# esc.net
KiCad netlist of a schematic drawn in EAGLE
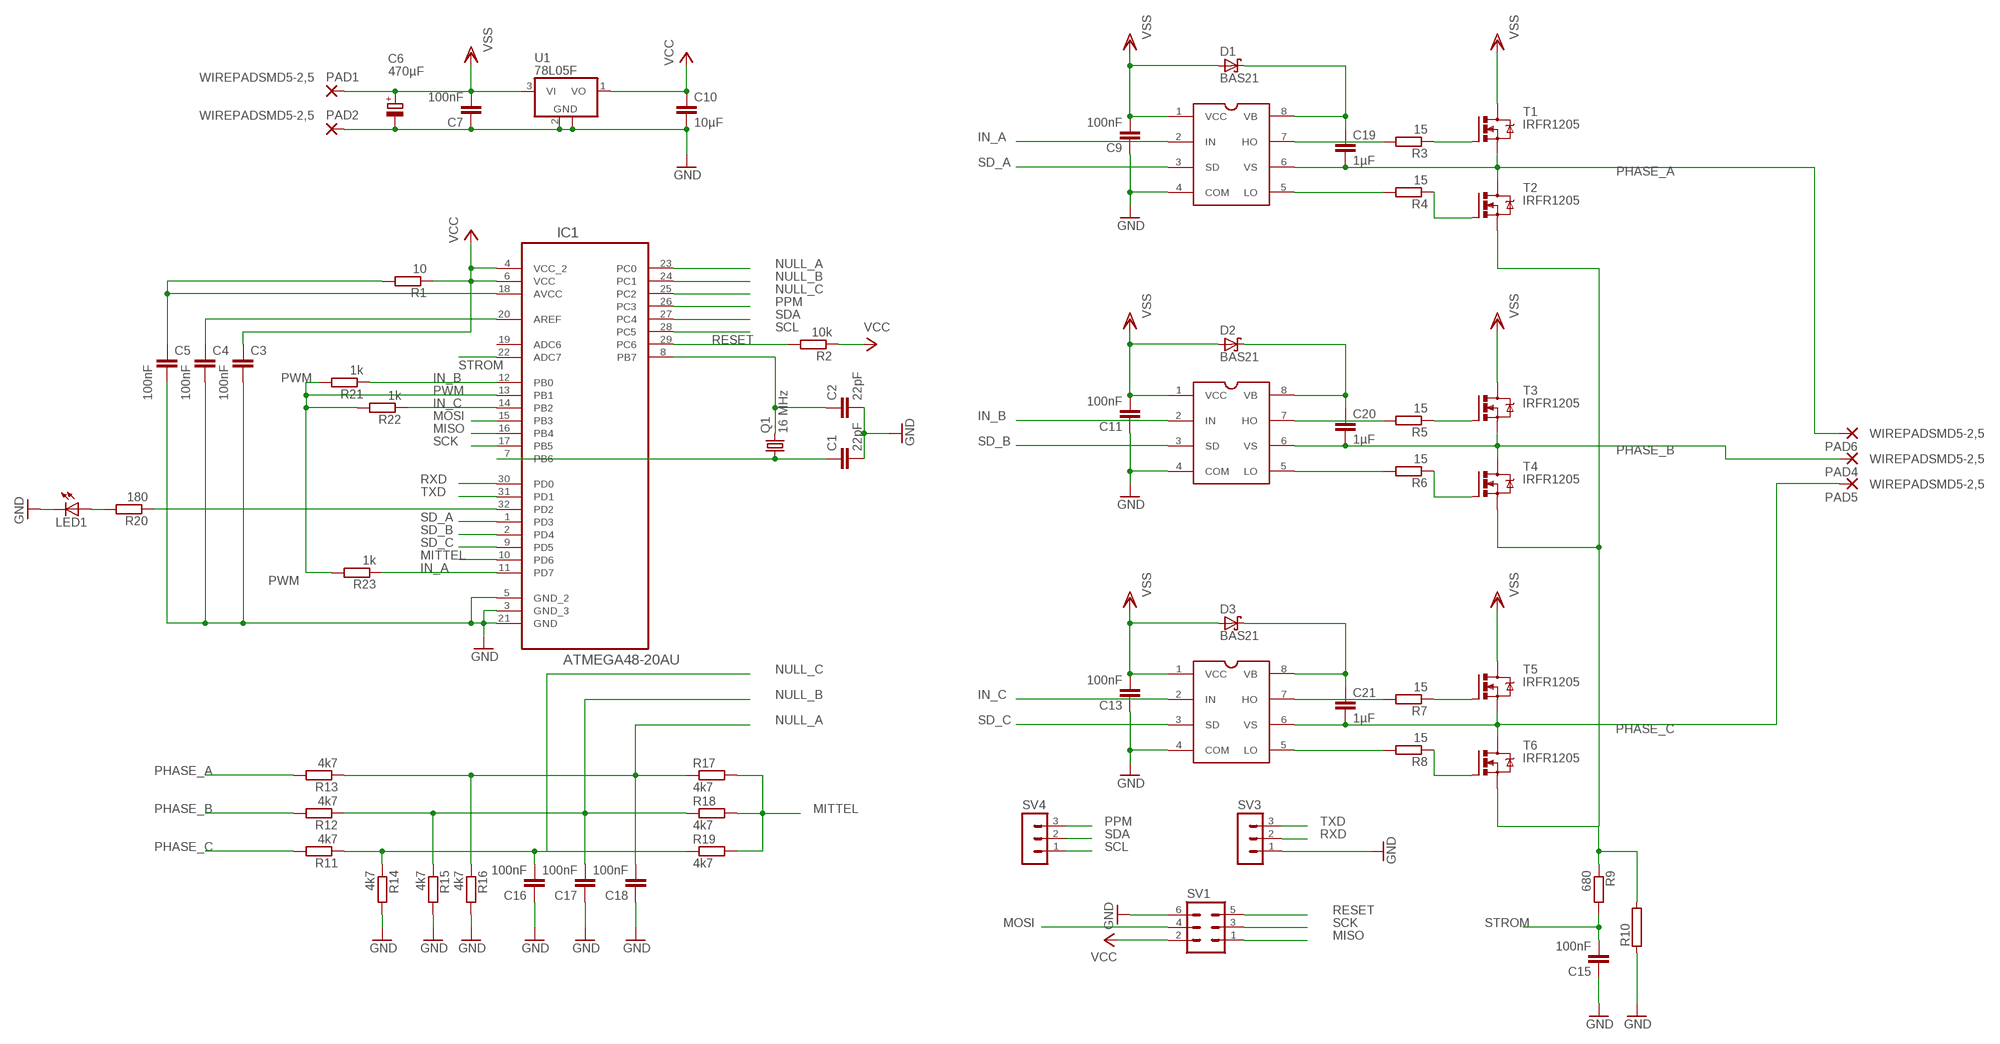
[diagram p0: schematic, sheet 1]

(export (version "E")
  (design (tool "Eeschema 10.0.6"))
  (components
    (comp (ref "C1")
      (value "22pF")
      (footprint "eagle-import:C1206")
      (libsource (lib "eagle-import") (part "C-EUC1206"))
    )
    (comp (ref "C2")
      (value "22pF")
      (footprint "eagle-import:C1206")
      (libsource (lib "eagle-import") (part "C-EUC1206"))
    )
    (comp (ref "C3")
      (value "100nF")
      (footprint "eagle-import:C1206")
      (libsource (lib "eagle-import") (part "C-EUC1206"))
    )
    (comp (ref "C4")
      (value "100nF")
      (footprint "eagle-import:C1206")
      (libsource (lib "eagle-import") (part "C-EUC1206"))
    )
    (comp (ref "C5")
      (value "100nF")
      (footprint "eagle-import:C1206")
      (libsource (lib "eagle-import") (part "C-EUC1206"))
    )
    (comp (ref "C6")
      (value "470µF")
      (footprint "eagle-import:E5-10,5")
      (libsource (lib "eagle-import") (part "CPOL-EUE5-10.5"))
    )
    (comp (ref "C7")
      (value "100nF")
      (footprint "eagle-import:C1206")
      (libsource (lib "eagle-import") (part "C-EUC1206"))
    )
    (comp (ref "C9")
      (value "100nF")
      (footprint "eagle-import:C1206")
      (libsource (lib "eagle-import") (part "C-EUC1206"))
    )
    (comp (ref "C10")
      (value "10µF")
      (footprint "eagle-import:C1206")
      (libsource (lib "eagle-import") (part "C-EUC1206"))
    )
    (comp (ref "C11")
      (value "100nF")
      (footprint "eagle-import:C1206")
      (libsource (lib "eagle-import") (part "C-EUC1206"))
    )
    (comp (ref "C13")
      (value "100nF")
      (footprint "eagle-import:C1206")
      (libsource (lib "eagle-import") (part "C-EUC1206"))
    )
    (comp (ref "C15")
      (value "100nF")
      (footprint "eagle-import:C1206")
      (libsource (lib "eagle-import") (part "C-EUC1206"))
    )
    (comp (ref "C16")
      (value "100nF")
      (footprint "eagle-import:C1206")
      (libsource (lib "eagle-import") (part "C-EUC1206"))
    )
    (comp (ref "C17")
      (value "100nF")
      (footprint "eagle-import:C1206")
      (libsource (lib "eagle-import") (part "C-EUC1206"))
    )
    (comp (ref "C18")
      (value "100nF")
      (footprint "eagle-import:C1206")
      (libsource (lib "eagle-import") (part "C-EUC1206"))
    )
    (comp (ref "C19")
      (value "1µF")
      (footprint "eagle-import:C1206")
      (libsource (lib "eagle-import") (part "C-EUC1206"))
    )
    (comp (ref "C20")
      (value "1µF")
      (footprint "eagle-import:C1206")
      (libsource (lib "eagle-import") (part "C-EUC1206"))
    )
    (comp (ref "C21")
      (value "1µF")
      (footprint "eagle-import:C1206")
      (libsource (lib "eagle-import") (part "C-EUC1206"))
    )
    (comp (ref "D1")
      (value "BAS21")
      (footprint "eagle-import:SOT23")
      (libsource (lib "eagle-import") (part "BAS40"))
    )
    (comp (ref "D2")
      (value "BAS21")
      (footprint "eagle-import:SOT23")
      (libsource (lib "eagle-import") (part "BAS40"))
    )
    (comp (ref "D3")
      (value "BAS21")
      (footprint "eagle-import:SOT23")
      (libsource (lib "eagle-import") (part "BAS40"))
    )
    (comp (ref "IC1")
      (value "ATMEGA48-20AU")
      (footprint "eagle-import:QFP80P900X900X120-32N")
      (libsource (lib "eagle-import") (part "ATMEGA48-20AU"))
    )
    (comp (ref "LED1")
      (value "LEDCHIPLED_1206")
      (footprint "eagle-import:CHIPLED_1206")
      (libsource (lib "eagle-import") (part "LEDCHIPLED_1206"))
    )
    (comp (ref "PAD1")
      (value "WIREPADSMD5-2,5")
      (footprint "eagle-import:5-2,5")
      (libsource (lib "eagle-import") (part "WIREPADSMD5-2,5"))
    )
    (comp (ref "PAD2")
      (value "WIREPADSMD5-2,5")
      (footprint "eagle-import:5-2,5")
      (libsource (lib "eagle-import") (part "WIREPADSMD5-2,5"))
    )
    (comp (ref "PAD4")
      (value "WIREPADSMD5-2,5")
      (footprint "eagle-import:5-2,5")
      (libsource (lib "eagle-import") (part "WIREPADSMD5-2,5"))
    )
    (comp (ref "PAD5")
      (value "WIREPADSMD5-2,5")
      (footprint "eagle-import:5-2,5")
      (libsource (lib "eagle-import") (part "WIREPADSMD5-2,5"))
    )
    (comp (ref "PAD6")
      (value "WIREPADSMD5-2,5")
      (footprint "eagle-import:5-2,5")
      (libsource (lib "eagle-import") (part "WIREPADSMD5-2,5"))
    )
    (comp (ref "Q1")
      (value "16 MHz")
      (footprint "eagle-import:HC49UP")
      (libsource (lib "eagle-import") (part "CRYSTALHC49UP"))
    )
    (comp (ref "R1")
      (value "10")
      (footprint "eagle-import:R1206")
      (libsource (lib "eagle-import") (part "R-EU_R1206"))
    )
    (comp (ref "R2")
      (value "10k")
      (footprint "eagle-import:R1206")
      (libsource (lib "eagle-import") (part "R-EU_R1206"))
    )
    (comp (ref "R3")
      (value "15")
      (footprint "eagle-import:R1206")
      (libsource (lib "eagle-import") (part "R-EU_R1206"))
    )
    (comp (ref "R4")
      (value "15")
      (footprint "eagle-import:R1206")
      (libsource (lib "eagle-import") (part "R-EU_R1206"))
    )
    (comp (ref "R5")
      (value "15")
      (footprint "eagle-import:R1206")
      (libsource (lib "eagle-import") (part "R-EU_R1206"))
    )
    (comp (ref "R6")
      (value "15")
      (footprint "eagle-import:R1206")
      (libsource (lib "eagle-import") (part "R-EU_R1206"))
    )
    (comp (ref "R7")
      (value "15")
      (footprint "eagle-import:R1206")
      (libsource (lib "eagle-import") (part "R-EU_R1206"))
    )
    (comp (ref "R8")
      (value "15")
      (footprint "eagle-import:R1206")
      (libsource (lib "eagle-import") (part "R-EU_R1206"))
    )
    (comp (ref "R9")
      (value "680")
      (footprint "eagle-import:R1206")
      (libsource (lib "eagle-import") (part "R-EU_R1206"))
    )
    (comp (ref "R10")
      (value "RCA5150")
      (footprint "eagle-import:CA5150")
      (libsource (lib "eagle-import") (part "RCA5150"))
    )
    (comp (ref "R11")
      (value "4k7")
      (footprint "eagle-import:R1206")
      (libsource (lib "eagle-import") (part "R-EU_R1206"))
    )
    (comp (ref "R12")
      (value "4k7")
      (footprint "eagle-import:R1206")
      (libsource (lib "eagle-import") (part "R-EU_R1206"))
    )
    (comp (ref "R13")
      (value "4k7")
      (footprint "eagle-import:R1206")
      (libsource (lib "eagle-import") (part "R-EU_R1206"))
    )
    (comp (ref "R14")
      (value "4k7")
      (footprint "eagle-import:R1206")
      (libsource (lib "eagle-import") (part "R-EU_R1206"))
    )
    (comp (ref "R15")
      (value "4k7")
      (footprint "eagle-import:R1206")
      (libsource (lib "eagle-import") (part "R-EU_R1206"))
    )
    (comp (ref "R16")
      (value "4k7")
      (footprint "eagle-import:R1206")
      (libsource (lib "eagle-import") (part "R-EU_R1206"))
    )
    (comp (ref "R17")
      (value "4k7")
      (footprint "eagle-import:R1206")
      (libsource (lib "eagle-import") (part "R-EU_R1206"))
    )
    (comp (ref "R18")
      (value "4k7")
      (footprint "eagle-import:R1206")
      (libsource (lib "eagle-import") (part "R-EU_R1206"))
    )
    (comp (ref "R19")
      (value "4k7")
      (footprint "eagle-import:R1206")
      (libsource (lib "eagle-import") (part "R-EU_R1206"))
    )
    (comp (ref "R20")
      (value "180")
      (footprint "eagle-import:R1206")
      (libsource (lib "eagle-import") (part "R-EU_R1206"))
    )
    (comp (ref "R21")
      (value "1k")
      (footprint "eagle-import:R1206")
      (libsource (lib "eagle-import") (part "R-EU_R1206"))
    )
    (comp (ref "R22")
      (value "1k")
      (footprint "eagle-import:R1206")
      (libsource (lib "eagle-import") (part "R-EU_R1206"))
    )
    (comp (ref "R23")
      (value "1k")
      (footprint "eagle-import:R1206")
      (libsource (lib "eagle-import") (part "R-EU_R1206"))
    )
    (comp (ref "SV1")
      (value "ML6")
      (footprint "eagle-import:ML6")
      (libsource (lib "eagle-import") (part "ML6"))
    )
    (comp (ref "SV3")
      (value "MA03-1")
      (footprint "eagle-import:MA03-1")
      (libsource (lib "eagle-import") (part "MA03-1"))
    )
    (comp (ref "SV4")
      (value "MA03-1")
      (footprint "eagle-import:MA03-1")
      (libsource (lib "eagle-import") (part "MA03-1"))
    )
    (comp (ref "T1")
      (value "IRFR1205")
      (footprint "eagle-import:DPACK")
      (libsource (lib "eagle-import") (part "IRFR1205"))
    )
    (comp (ref "T2")
      (value "IRFR1205")
      (footprint "eagle-import:DPACK")
      (libsource (lib "eagle-import") (part "IRFR1205"))
    )
    (comp (ref "T3")
      (value "IRFR1205")
      (footprint "eagle-import:DPACK")
      (libsource (lib "eagle-import") (part "IRFR1205"))
    )
    (comp (ref "T4")
      (value "IRFR1205")
      (footprint "eagle-import:DPACK")
      (libsource (lib "eagle-import") (part "IRFR1205"))
    )
    (comp (ref "T5")
      (value "IRFR1205")
      (footprint "eagle-import:DPACK")
      (libsource (lib "eagle-import") (part "IRFR1205"))
    )
    (comp (ref "T6")
      (value "IRFR1205")
      (footprint "eagle-import:DPACK")
      (libsource (lib "eagle-import") (part "IRFR1205"))
    )
    (comp (ref "U$1")
      (value "IR2104S")
      (footprint "eagle-import:IR2104S")
      (libsource (lib "eagle-import") (part "IR2104S"))
    )
    (comp (ref "U$2")
      (value "IR2104S")
      (footprint "eagle-import:IR2104S")
      (libsource (lib "eagle-import") (part "IR2104S"))
    )
    (comp (ref "U$3")
      (value "IR2104S")
      (footprint "eagle-import:IR2104S")
      (libsource (lib "eagle-import") (part "IR2104S"))
    )
    (comp (ref "U1")
      (value "78L05F")
      (footprint "eagle-import:SOT89")
      (libsource (lib "eagle-import") (part "78LF05"))
    )
  )
  (nets
    (net (code "1") (name "/IN_A") (class "Default")
      (node (ref "IC1") (pin "11") (pinfunction "PD7_11") (pintype "bidirectional"))
      (node (ref "R23") (pin "1") (pinfunction "1_1") (pintype "passive"))
      (node (ref "U$1") (pin "2") (pinfunction "IN_2") (pintype "bidirectional"))
    )
    (net (code "2") (name "/IN_B") (class "Default")
      (node (ref "IC1") (pin "12") (pinfunction "PB0_12") (pintype "bidirectional"))
      (node (ref "R21") (pin "1") (pinfunction "1_1") (pintype "passive"))
      (node (ref "U$2") (pin "2") (pinfunction "IN_2") (pintype "bidirectional"))
    )
    (net (code "3") (name "/IN_C") (class "Default")
      (node (ref "IC1") (pin "14") (pinfunction "PB2_14") (pintype "bidirectional"))
      (node (ref "R22") (pin "1") (pinfunction "1_1") (pintype "passive"))
      (node (ref "U$3") (pin "2") (pinfunction "IN_2") (pintype "bidirectional"))
    )
    (net (code "4") (name "/MISO") (class "Default")
      (node (ref "IC1") (pin "16") (pinfunction "PB4_16") (pintype "bidirectional"))
      (node (ref "SV1") (pin "1") (pinfunction "1_1") (pintype "passive"))
    )
    (net (code "5") (name "/MITTEL") (class "Default")
      (node (ref "IC1") (pin "10") (pinfunction "PD6_10") (pintype "bidirectional"))
      (node (ref "R17") (pin "2") (pinfunction "2_2") (pintype "passive"))
      (node (ref "R18") (pin "2") (pinfunction "2_2") (pintype "passive"))
      (node (ref "R19") (pin "2") (pinfunction "2_2") (pintype "passive"))
    )
    (net (code "6") (name "/MOSI") (class "Default")
      (node (ref "IC1") (pin "15") (pinfunction "PB3_15") (pintype "bidirectional"))
      (node (ref "SV1") (pin "4") (pinfunction "4_4") (pintype "passive"))
    )
    (net (code "7") (name "/NULL_A") (class "Default")
      (node (ref "C18") (pin "2") (pinfunction "2_2") (pintype "passive"))
      (node (ref "IC1") (pin "23") (pinfunction "PC0_23") (pintype "bidirectional"))
      (node (ref "R13") (pin "1") (pinfunction "1_1") (pintype "passive"))
      (node (ref "R16") (pin "1") (pinfunction "1_1") (pintype "passive"))
      (node (ref "R17") (pin "1") (pinfunction "1_1") (pintype "passive"))
    )
    (net (code "8") (name "/NULL_B") (class "Default")
      (node (ref "C17") (pin "2") (pinfunction "2_2") (pintype "passive"))
      (node (ref "IC1") (pin "24") (pinfunction "PC1_24") (pintype "bidirectional"))
      (node (ref "R12") (pin "1") (pinfunction "1_1") (pintype "passive"))
      (node (ref "R15") (pin "1") (pinfunction "1_1") (pintype "passive"))
      (node (ref "R18") (pin "1") (pinfunction "1_1") (pintype "passive"))
    )
    (net (code "9") (name "/NULL_C") (class "Default")
      (node (ref "C16") (pin "2") (pinfunction "2_2") (pintype "passive"))
      (node (ref "IC1") (pin "25") (pinfunction "PC2_25") (pintype "bidirectional"))
      (node (ref "R11") (pin "1") (pinfunction "1_1") (pintype "passive"))
      (node (ref "R14") (pin "1") (pinfunction "1_1") (pintype "passive"))
      (node (ref "R19") (pin "1") (pinfunction "1_1") (pintype "passive"))
    )
    (net (code "10") (name "/PHASE_A") (class "Default")
      (node (ref "C19") (pin "2") (pinfunction "2_2") (pintype "passive"))
      (node (ref "PAD6") (pin "1") (pinfunction "P_1") (pintype "passive"))
      (node (ref "R13") (pin "2") (pinfunction "2_2") (pintype "passive"))
      (node (ref "T1") (pin "3") (pinfunction "S_3") (pintype "passive"))
      (node (ref "T2") (pin "2") (pinfunction "D_2") (pintype "passive"))
      (node (ref "U$1") (pin "6") (pinfunction "VS_6") (pintype "power_in"))
    )
    (net (code "11") (name "/PHASE_B") (class "Default")
      (node (ref "C20") (pin "2") (pinfunction "2_2") (pintype "passive"))
      (node (ref "PAD4") (pin "1") (pinfunction "P_1") (pintype "passive"))
      (node (ref "R12") (pin "2") (pinfunction "2_2") (pintype "passive"))
      (node (ref "T3") (pin "3") (pinfunction "S_3") (pintype "passive"))
      (node (ref "T4") (pin "2") (pinfunction "D_2") (pintype "passive"))
      (node (ref "U$2") (pin "6") (pinfunction "VS_6") (pintype "power_in"))
    )
    (net (code "12") (name "/PHASE_C") (class "Default")
      (node (ref "C21") (pin "2") (pinfunction "2_2") (pintype "passive"))
      (node (ref "PAD5") (pin "1") (pinfunction "P_1") (pintype "passive"))
      (node (ref "R11") (pin "2") (pinfunction "2_2") (pintype "passive"))
      (node (ref "T5") (pin "3") (pinfunction "S_3") (pintype "passive"))
      (node (ref "T6") (pin "2") (pinfunction "D_2") (pintype "passive"))
      (node (ref "U$3") (pin "6") (pinfunction "VS_6") (pintype "power_in"))
    )
    (net (code "13") (name "/PPM") (class "Default")
      (node (ref "IC1") (pin "26") (pinfunction "PC3_26") (pintype "bidirectional"))
      (node (ref "SV4") (pin "3") (pinfunction "3_3") (pintype "passive"))
    )
    (net (code "14") (name "/PWM") (class "Default")
      (node (ref "IC1") (pin "13") (pinfunction "PB1_13") (pintype "bidirectional"))
      (node (ref "R21") (pin "2") (pinfunction "2_2") (pintype "passive"))
      (node (ref "R22") (pin "2") (pinfunction "2_2") (pintype "passive"))
      (node (ref "R23") (pin "2") (pinfunction "2_2") (pintype "passive"))
    )
    (net (code "15") (name "/RESET") (class "Default")
      (node (ref "IC1") (pin "29") (pinfunction "PC6_29") (pintype "bidirectional"))
      (node (ref "R2") (pin "2") (pinfunction "2_2") (pintype "passive"))
      (node (ref "SV1") (pin "5") (pinfunction "5_5") (pintype "passive"))
    )
    (net (code "16") (name "/RXD") (class "Default")
      (node (ref "IC1") (pin "30") (pinfunction "PD0_30") (pintype "bidirectional"))
      (node (ref "SV3") (pin "2") (pinfunction "2_2") (pintype "passive"))
    )
    (net (code "17") (name "/SCK") (class "Default")
      (node (ref "IC1") (pin "17") (pinfunction "PB5_17") (pintype "bidirectional"))
      (node (ref "SV1") (pin "3") (pinfunction "3_3") (pintype "passive"))
    )
    (net (code "18") (name "/SCL") (class "Default")
      (node (ref "IC1") (pin "28") (pinfunction "PC5_28") (pintype "bidirectional"))
      (node (ref "SV4") (pin "1") (pinfunction "1_1") (pintype "passive"))
    )
    (net (code "19") (name "/SDA") (class "Default")
      (node (ref "IC1") (pin "27") (pinfunction "PC4_27") (pintype "bidirectional"))
      (node (ref "SV4") (pin "2") (pinfunction "2_2") (pintype "passive"))
    )
    (net (code "20") (name "/SD_A") (class "Default")
      (node (ref "IC1") (pin "1") (pinfunction "PD3_1") (pintype "bidirectional"))
      (node (ref "U$1") (pin "3") (pinfunction "SD_3") (pintype "bidirectional"))
    )
    (net (code "21") (name "/SD_B") (class "Default")
      (node (ref "IC1") (pin "2") (pinfunction "PD4_2") (pintype "bidirectional"))
      (node (ref "U$2") (pin "3") (pinfunction "SD_3") (pintype "bidirectional"))
    )
    (net (code "22") (name "/SD_C") (class "Default")
      (node (ref "IC1") (pin "9") (pinfunction "PD5_9") (pintype "bidirectional"))
      (node (ref "U$3") (pin "3") (pinfunction "SD_3") (pintype "bidirectional"))
    )
    (net (code "23") (name "/STROM") (class "Default")
      (node (ref "C15") (pin "2") (pinfunction "2_2") (pintype "passive"))
      (node (ref "IC1") (pin "22") (pinfunction "ADC7_22") (pintype "input"))
      (node (ref "R9") (pin "2") (pinfunction "2_2") (pintype "passive"))
    )
    (net (code "24") (name "/TXD") (class "Default")
      (node (ref "IC1") (pin "31") (pinfunction "PD1_31") (pintype "bidirectional"))
      (node (ref "SV3") (pin "3") (pinfunction "3_3") (pintype "passive"))
    )
    (net (code "25") (name "GND") (class "Default")
      (node (ref "C1") (pin "2") (pinfunction "2_2") (pintype "passive"))
      (node (ref "C10") (pin "2") (pinfunction "2_2") (pintype "passive"))
      (node (ref "C11") (pin "1") (pinfunction "1_1") (pintype "passive"))
      (node (ref "C13") (pin "1") (pinfunction "1_1") (pintype "passive"))
      (node (ref "C15") (pin "1") (pinfunction "1_1") (pintype "passive"))
      (node (ref "C16") (pin "1") (pinfunction "1_1") (pintype "passive"))
      (node (ref "C17") (pin "1") (pinfunction "1_1") (pintype "passive"))
      (node (ref "C18") (pin "1") (pinfunction "1_1") (pintype "passive"))
      (node (ref "C2") (pin "2") (pinfunction "2_2") (pintype "passive"))
      (node (ref "C3") (pin "2") (pinfunction "2_2") (pintype "passive"))
      (node (ref "C4") (pin "2") (pinfunction "2_2") (pintype "passive"))
      (node (ref "C5") (pin "2") (pinfunction "2_2") (pintype "passive"))
      (node (ref "C6") (pin "-") (pinfunction "-_-") (pintype "passive"))
      (node (ref "C7") (pin "1") (pinfunction "1_1") (pintype "passive"))
      (node (ref "C9") (pin "1") (pinfunction "1_1") (pintype "passive"))
      (node (ref "IC1") (pin "21") (pinfunction "GND_21") (pintype "passive"))
      (node (ref "IC1") (pin "3") (pinfunction "GND_3_3") (pintype "passive"))
      (node (ref "IC1") (pin "5") (pinfunction "GND_2_5") (pintype "passive"))
      (node (ref "LED1") (pin "C") (pinfunction "C_C") (pintype "passive"))
      (node (ref "PAD2") (pin "1") (pinfunction "P_1") (pintype "passive"))
      (node (ref "R10") (pin "1") (pinfunction "1_1") (pintype "passive"))
      (node (ref "R14") (pin "2") (pinfunction "2_2") (pintype "passive"))
      (node (ref "R15") (pin "2") (pinfunction "2_2") (pintype "passive"))
      (node (ref "R16") (pin "2") (pinfunction "2_2") (pintype "passive"))
      (node (ref "SV1") (pin "6") (pinfunction "6_6") (pintype "passive"))
      (node (ref "SV3") (pin "1") (pinfunction "1_1") (pintype "passive"))
      (node (ref "U$1") (pin "4") (pinfunction "COM_4") (pintype "bidirectional"))
      (node (ref "U$2") (pin "4") (pinfunction "COM_4") (pintype "bidirectional"))
      (node (ref "U$3") (pin "4") (pinfunction "COM_4") (pintype "bidirectional"))
      (node (ref "U1") (pin "2") (pinfunction "GND_2") (pintype "passive"))
      (node (ref "U1") (pin "2@1") (pinfunction "GND_2@1") (pintype "passive"))
    )
    (net (code "26") (name "Net-(D1-C)") (class "Default")
      (node (ref "C19") (pin "1") (pinfunction "1_1") (pintype "passive"))
      (node (ref "D1") (pin "3") (pinfunction "C_3") (pintype "passive"))
      (node (ref "U$1") (pin "8") (pinfunction "VB_8") (pintype "power_in"))
    )
    (net (code "27") (name "Net-(D2-C)") (class "Default")
      (node (ref "C20") (pin "1") (pinfunction "1_1") (pintype "passive"))
      (node (ref "D2") (pin "3") (pinfunction "C_3") (pintype "passive"))
      (node (ref "U$2") (pin "8") (pinfunction "VB_8") (pintype "power_in"))
    )
    (net (code "28") (name "Net-(D3-C)") (class "Default")
      (node (ref "C21") (pin "1") (pinfunction "1_1") (pintype "passive"))
      (node (ref "D3") (pin "3") (pinfunction "C_3") (pintype "passive"))
      (node (ref "U$3") (pin "8") (pinfunction "VB_8") (pintype "power_in"))
    )
    (net (code "29") (name "Net-(IC1-AREF)") (class "Default")
      (node (ref "C4") (pin "1") (pinfunction "1_1") (pintype "passive"))
      (node (ref "IC1") (pin "20") (pinfunction "AREF_20") (pintype "input"))
    )
    (net (code "30") (name "Net-(IC1-AVCC)") (class "Default")
      (node (ref "C5") (pin "1") (pinfunction "1_1") (pintype "passive"))
      (node (ref "IC1") (pin "18") (pinfunction "AVCC_18") (pintype "power_in"))
      (node (ref "R1") (pin "2") (pinfunction "2_2") (pintype "passive"))
    )
    (net (code "31") (name "Net-(IC1-PB6)") (class "Default")
      (node (ref "C1") (pin "1") (pinfunction "1_1") (pintype "passive"))
      (node (ref "IC1") (pin "7") (pinfunction "PB6_7") (pintype "bidirectional"))
      (node (ref "Q1") (pin "1") (pinfunction "1_1") (pintype "passive"))
    )
    (net (code "32") (name "Net-(IC1-PB7)") (class "Default")
      (node (ref "C2") (pin "1") (pinfunction "1_1") (pintype "passive"))
      (node (ref "IC1") (pin "8") (pinfunction "PB7_8") (pintype "bidirectional"))
      (node (ref "Q1") (pin "2") (pinfunction "2_2") (pintype "passive"))
    )
    (net (code "33") (name "Net-(IC1-PD2)") (class "Default")
      (node (ref "IC1") (pin "32") (pinfunction "PD2_32") (pintype "bidirectional"))
      (node (ref "R20") (pin "1") (pinfunction "1_1") (pintype "passive"))
    )
    (net (code "34") (name "Net-(LED1-PadA)") (class "Default")
      (node (ref "LED1") (pin "A") (pinfunction "A_A") (pintype "passive"))
      (node (ref "R20") (pin "2") (pinfunction "2_2") (pintype "passive"))
    )
    (net (code "35") (name "Net-(T1-G)") (class "Default")
      (node (ref "R3") (pin "1") (pinfunction "1_1") (pintype "passive"))
      (node (ref "T1") (pin "1") (pinfunction "G_1") (pintype "passive"))
    )
    (net (code "36") (name "Net-(T2-G)") (class "Default")
      (node (ref "R4") (pin "1") (pinfunction "1_1") (pintype "passive"))
      (node (ref "T2") (pin "1") (pinfunction "G_1") (pintype "passive"))
    )
    (net (code "37") (name "Net-(T2-S)") (class "Default")
      (node (ref "R10") (pin "2") (pinfunction "2_2") (pintype "passive"))
      (node (ref "R9") (pin "1") (pinfunction "1_1") (pintype "passive"))
      (node (ref "T2") (pin "3") (pinfunction "S_3") (pintype "passive"))
      (node (ref "T4") (pin "3") (pinfunction "S_3") (pintype "passive"))
      (node (ref "T6") (pin "3") (pinfunction "S_3") (pintype "passive"))
    )
    (net (code "38") (name "Net-(T3-G)") (class "Default")
      (node (ref "R5") (pin "1") (pinfunction "1_1") (pintype "passive"))
      (node (ref "T3") (pin "1") (pinfunction "G_1") (pintype "passive"))
    )
    (net (code "39") (name "Net-(T4-G)") (class "Default")
      (node (ref "R6") (pin "1") (pinfunction "1_1") (pintype "passive"))
      (node (ref "T4") (pin "1") (pinfunction "G_1") (pintype "passive"))
    )
    (net (code "40") (name "Net-(T5-G)") (class "Default")
      (node (ref "R7") (pin "1") (pinfunction "1_1") (pintype "passive"))
      (node (ref "T5") (pin "1") (pinfunction "G_1") (pintype "passive"))
    )
    (net (code "41") (name "Net-(T6-G)") (class "Default")
      (node (ref "R8") (pin "1") (pinfunction "1_1") (pintype "passive"))
      (node (ref "T6") (pin "1") (pinfunction "G_1") (pintype "passive"))
    )
    (net (code "42") (name "Net-(U$1-HO)") (class "Default")
      (node (ref "R3") (pin "2") (pinfunction "2_2") (pintype "passive"))
      (node (ref "U$1") (pin "7") (pinfunction "HO_7") (pintype "bidirectional"))
    )
    (net (code "43") (name "Net-(U$1-LO)") (class "Default")
      (node (ref "R4") (pin "2") (pinfunction "2_2") (pintype "passive"))
      (node (ref "U$1") (pin "5") (pinfunction "LO_5") (pintype "bidirectional"))
    )
    (net (code "44") (name "Net-(U$2-HO)") (class "Default")
      (node (ref "R5") (pin "2") (pinfunction "2_2") (pintype "passive"))
      (node (ref "U$2") (pin "7") (pinfunction "HO_7") (pintype "bidirectional"))
    )
    (net (code "45") (name "Net-(U$2-LO)") (class "Default")
      (node (ref "R6") (pin "2") (pinfunction "2_2") (pintype "passive"))
      (node (ref "U$2") (pin "5") (pinfunction "LO_5") (pintype "bidirectional"))
    )
    (net (code "46") (name "Net-(U$3-HO)") (class "Default")
      (node (ref "R7") (pin "2") (pinfunction "2_2") (pintype "passive"))
      (node (ref "U$3") (pin "7") (pinfunction "HO_7") (pintype "bidirectional"))
    )
    (net (code "47") (name "Net-(U$3-LO)") (class "Default")
      (node (ref "R8") (pin "2") (pinfunction "2_2") (pintype "passive"))
      (node (ref "U$3") (pin "5") (pinfunction "LO_5") (pintype "bidirectional"))
    )
    (net (code "48") (name "VCC") (class "Default")
      (node (ref "C10") (pin "1") (pinfunction "1_1") (pintype "passive"))
      (node (ref "C3") (pin "1") (pinfunction "1_1") (pintype "passive"))
      (node (ref "IC1") (pin "4") (pinfunction "VCC_2_4") (pintype "power_in"))
      (node (ref "IC1") (pin "6") (pinfunction "VCC_6") (pintype "power_in"))
      (node (ref "R1") (pin "1") (pinfunction "1_1") (pintype "passive"))
      (node (ref "R2") (pin "1") (pinfunction "1_1") (pintype "passive"))
      (node (ref "SV1") (pin "2") (pinfunction "2_2") (pintype "passive"))
      (node (ref "U1") (pin "1") (pinfunction "VO_1") (pintype "passive"))
    )
    (net (code "49") (name "VSS") (class "Default")
      (node (ref "C11") (pin "2") (pinfunction "2_2") (pintype "passive"))
      (node (ref "C13") (pin "2") (pinfunction "2_2") (pintype "passive"))
      (node (ref "C6") (pin "+") (pinfunction "+_+") (pintype "passive"))
      (node (ref "C7") (pin "2") (pinfunction "2_2") (pintype "passive"))
      (node (ref "C9") (pin "2") (pinfunction "2_2") (pintype "passive"))
      (node (ref "D1") (pin "1") (pinfunction "A_1") (pintype "passive"))
      (node (ref "D2") (pin "1") (pinfunction "A_1") (pintype "passive"))
      (node (ref "D3") (pin "1") (pinfunction "A_1") (pintype "passive"))
      (node (ref "PAD1") (pin "1") (pinfunction "P_1") (pintype "passive"))
      (node (ref "T1") (pin "2") (pinfunction "D_2") (pintype "passive"))
      (node (ref "T3") (pin "2") (pinfunction "D_2") (pintype "passive"))
      (node (ref "T5") (pin "2") (pinfunction "D_2") (pintype "passive"))
      (node (ref "U$1") (pin "1") (pinfunction "VCC_1") (pintype "power_in"))
      (node (ref "U$2") (pin "1") (pinfunction "VCC_1") (pintype "power_in"))
      (node (ref "U$3") (pin "1") (pinfunction "VCC_1") (pintype "power_in"))
      (node (ref "U1") (pin "3") (pinfunction "VI_3") (pintype "input"))
    )
    (net (code "50") (name "unconnected-(IC1-ADC6-Pad19)") (class "Default")
      (node (ref "IC1") (pin "19") (pinfunction "ADC6_19") (pintype "input"))
    )
  )
)
